# DriverForDisplayV2.net
KiCad netlist of a schematic drawn in Altium Designer
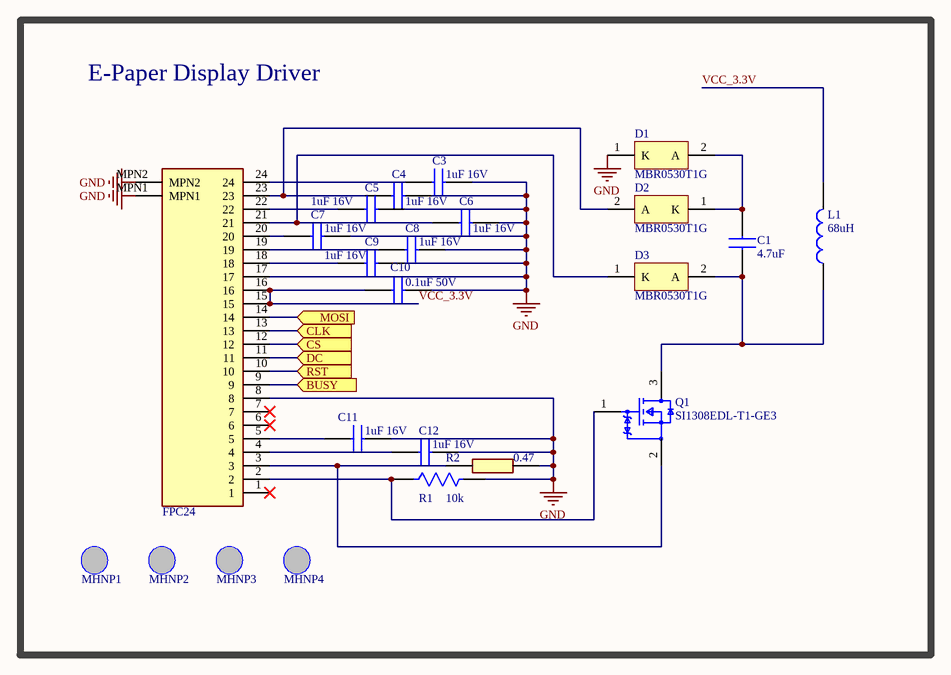
[diagram p0: DriverForDisplayV2.SchDoc]

(export (version "E")
  (design (tool "Eeschema 10.0.6"))
  (components
    (comp (ref "C1")
      (value "4.7uF")
      (footprint "SamacSys:CAPC1608X90N")
      (description "Capacitor")
      (fields
        (field (name "MANUFACTURER_PART_NUMBER") "CL10A475KO8NNNC")
        (field (name "MOUSER PART NUMBER") "187-CL10A475KO8NNNC")
      )
      (libsource (lib "*") (part "CL10A475KO8NNNC"))
    )
    (comp (ref "C3")
      (value "1uF 16V")
      (footprint "CAPC1608X90N")
      (fields
        (field (name "MANUFACTURER_PART_NUMBER") "CL10A105KO8NNNC")
        (field (name "MOUSER PART NUMBER") "187-CL10A105KO8NNNC")
      )
      (libsource (lib "Integrated_Library1") (part "CL10A105KO8NNNC"))
    )
    (comp (ref "C4")
      (value "1uF 16V")
      (footprint "CAPC1608X90N")
      (fields
        (field (name "MANUFACTURER_PART_NUMBER") "CL10A105KO8NNNC")
        (field (name "MOUSER PART NUMBER") "187-CL10A105KO8NNNC")
      )
      (libsource (lib "Integrated_Library1") (part "CL10A105KO8NNNC"))
    )
    (comp (ref "C5")
      (value "1uF 16V")
      (footprint "CAPC1608X90N")
      (fields
        (field (name "MANUFACTURER_PART_NUMBER") "CL10A105KO8NNNC")
        (field (name "MOUSER PART NUMBER") "187-CL10A105KO8NNNC")
      )
      (libsource (lib "Integrated_Library1") (part "CL10A105KO8NNNC"))
    )
    (comp (ref "C6")
      (value "1uF 16V")
      (footprint "CAPC1608X90N")
      (fields
        (field (name "MANUFACTURER_PART_NUMBER") "CL10A105KO8NNNC")
        (field (name "MOUSER PART NUMBER") "187-CL10A105KO8NNNC")
      )
      (libsource (lib "Integrated_Library1") (part "CL10A105KO8NNNC"))
    )
    (comp (ref "C7")
      (value "1uF 16V")
      (footprint "CAPC1608X90N")
      (fields
        (field (name "MANUFACTURER_PART_NUMBER") "CL10A105KO8NNNC")
        (field (name "MOUSER PART NUMBER") "187-CL10A105KO8NNNC")
      )
      (libsource (lib "Integrated_Library1") (part "CL10A105KO8NNNC"))
    )
    (comp (ref "C8")
      (value "1uF 16V")
      (footprint "CAPC1608X90N")
      (fields
        (field (name "MANUFACTURER_PART_NUMBER") "CL10A105KO8NNNC")
        (field (name "MOUSER PART NUMBER") "187-CL10A105KO8NNNC")
      )
      (libsource (lib "Integrated_Library1") (part "CL10A105KO8NNNC"))
    )
    (comp (ref "C9")
      (value "1uF 16V")
      (footprint "CAPC1608X90N")
      (fields
        (field (name "MANUFACTURER_PART_NUMBER") "CL10A105KO8NNNC")
        (field (name "MOUSER PART NUMBER") "187-CL10A105KO8NNNC")
      )
      (libsource (lib "Integrated_Library1") (part "CL10A105KO8NNNC"))
    )
    (comp (ref "C10")
      (value "0.1uF 50V")
      (footprint "CAPC1608X90N")
      (fields
        (field (name "MANUFACTURER_PART_NUMBER") "CL10A105KO8NNNC")
        (field (name "MOUSER PART NUMBER") "187-CL10A105KO8NNNC")
      )
      (libsource (lib "Integrated_Library1") (part "CL10A105KO8NNNC"))
    )
    (comp (ref "C11")
      (value "1uF 16V")
      (footprint "CAPC1608X90N")
      (fields
        (field (name "MANUFACTURER_PART_NUMBER") "CL10A105KO8NNNC")
        (field (name "MOUSER PART NUMBER") "187-CL10A105KO8NNNC")
      )
      (libsource (lib "Integrated_Library1") (part "CL10A105KO8NNNC"))
    )
    (comp (ref "C12")
      (value "1uF 16V")
      (footprint "CAPC1608X90N")
      (fields
        (field (name "MANUFACTURER_PART_NUMBER") "CL10A105KO8NNNC")
        (field (name "MOUSER PART NUMBER") "187-CL10A105KO8NNNC")
      )
      (libsource (lib "Integrated_Library1") (part "CL10A105KO8NNNC"))
    )
    (comp (ref "D1")
      (value "MBR0530T1G")
      (footprint "ONSC-SOD-123-2-425-04_V")
      (fields (field (name "MANUFACTURER") "On Semiconductor"))
      (libsource (lib "Altium Content Vault") (part "ONSC-D-K1A2-2_A"))
    )
    (comp (ref "D2")
      (value "MBR0530T1G")
      (footprint "ONSC-SOD-123-2-425-04_V")
      (fields (field (name "MANUFACTURER") "On Semiconductor"))
      (libsource (lib "") (part "ONSC-D-K1A2-2_A_1"))
    )
    (comp (ref "D3")
      (value "MBR0530T1G")
      (footprint "ONSC-SOD-123-2-425-04_V")
      (fields (field (name "MANUFACTURER") "On Semiconductor"))
      (libsource (lib "Altium Content Vault") (part "ONSC-D-K1A2-2_A"))
    )
    (comp (ref "J2")
      (value "FPC24")
      (footprint "SamacSys:FH34SRJ24S05SH50")
      (description "Connector")
      (fields
        (field (name "MANUFACTURER_PART_NUMBER") "FH34SRJ-24S-0.5SH(50)")
        (field (name "MOUSER PART NUMBER") "798-FH34SRJ24S05SH50")
      )
      (libsource (lib "*") (part "FH34SRJ-24S-0.5SH_50_"))
    )
    (comp (ref "L1")
      (value "68uH")
      (footprint "SamacSys:INDC2012X145N")
      (description "Inductor")
      (fields
        (field (name "MANUFACTURER_PART_NUMBER") "MLF2012C680KT000")
        (field (name "MOUSER PART NUMBER") "810-MLF2012C680KT000")
      )
      (libsource (lib "*") (part "MLF2012C680KT000"))
    )
    (comp (ref "MHNP1")
      (value "CMP-011-000000-1")
      (footprint "MTHNP3P2MM")
      (description "Mounting Hole Non-Plated 3.2 mm drill hole")
      (libsource (lib "timothy") (part "MTHNP3P2MM"))
    )
    (comp (ref "MHNP2")
      (value "CMP-011-000000-1")
      (footprint "MTHNP3P2MM")
      (description "Mounting Hole Non-Plated 3.2 mm drill hole")
      (libsource (lib "timothy") (part "MTHNP3P2MM"))
    )
    (comp (ref "MHNP3")
      (value "CMP-011-000000-1")
      (footprint "MTHNP3P2MM")
      (description "Mounting Hole Non-Plated 3.2 mm drill hole")
      (libsource (lib "timothy") (part "MTHNP3P2MM"))
    )
    (comp (ref "MHNP4")
      (value "CMP-011-000000-1")
      (footprint "MTHNP3P2MM")
      (description "Mounting Hole Non-Plated 3.2 mm drill hole")
      (libsource (lib "timothy") (part "MTHNP3P2MM"))
    )
    (comp (ref "Q1")
      (value "SI1308EDL-T1-GE3")
      (footprint "FP-5549-MFG")
      (description "MOSFET N-CH 30V 1.4A SC-70-3")
      (libsource (lib "Altium Content Vault") (part "e96677422f20f20903245877d22b385"))
    )
    (comp (ref "R1")
      (value "10k")
      (footprint "FP-RC1608-MFG")
      (description "Res Thick Film 0603 10kΩ 1% 0.1W ±100ppm/°C Molded SMD T/R")
      (fields (field (name "TOLERANCE") "1%"))
      (libsource (lib "Altium Content Vault") (part "1029c3af85768c4190bb7ad29bc67b5"))
    )
    (comp (ref "R2")
      (value "0.47")
      (footprint "SamacSys:RESC1608X55N")
      (description "RES, 0603, 0.47 ohm, 5%, 0.1W")
      (fields (field (name "MANUFACTURER_PART_NUMBER") "RMCF0603JTR470"))
      (libsource (lib "*") (part "RMCF0603JTR470"))
    )
  )
  (nets
    (net (code "1") (name "/BUSY") (class "Default")
      (node (ref "J2") (pin "9") (pinfunction "9_9") (pintype "passive"))
    )
    (net (code "2") (name "/CLK") (class "Default")
      (node (ref "J2") (pin "13") (pinfunction "13_13") (pintype "passive"))
    )
    (net (code "3") (name "/CS") (class "Default")
      (node (ref "J2") (pin "12") (pinfunction "12_12") (pintype "passive"))
    )
    (net (code "4") (name "/DC") (class "Default")
      (node (ref "J2") (pin "11") (pinfunction "11_11") (pintype "passive"))
    )
    (net (code "5") (name "/MOSI") (class "Default")
      (node (ref "J2") (pin "14") (pinfunction "14_14") (pintype "passive"))
    )
    (net (code "6") (name "/RST") (class "Default")
      (node (ref "J2") (pin "10") (pinfunction "10_10") (pintype "passive"))
    )
    (net (code "7") (name "/VCC_3.3V") (class "Default")
      (node (ref "C10") (pin "1") (pinfunction "1_1") (pintype "passive"))
      (node (ref "J2") (pin "15") (pinfunction "15_15") (pintype "passive"))
      (node (ref "J2") (pin "16") (pinfunction "16_16") (pintype "passive"))
      (node (ref "L1") (pin "2") (pinfunction "2_2") (pintype "passive"))
    )
    (net (code "8") (name "GND") (class "Default")
      (node (ref "C10") (pin "2") (pinfunction "2_2") (pintype "passive"))
      (node (ref "C11") (pin "2") (pinfunction "2_2") (pintype "passive"))
      (node (ref "C12") (pin "2") (pinfunction "2_2") (pintype "passive"))
      (node (ref "C3") (pin "2") (pinfunction "2_2") (pintype "passive"))
      (node (ref "C4") (pin "2") (pinfunction "2_2") (pintype "passive"))
      (node (ref "C5") (pin "2") (pinfunction "2_2") (pintype "passive"))
      (node (ref "C6") (pin "2") (pinfunction "2_2") (pintype "passive"))
      (node (ref "C7") (pin "2") (pinfunction "2_2") (pintype "passive"))
      (node (ref "C8") (pin "2") (pinfunction "2_2") (pintype "passive"))
      (node (ref "C9") (pin "2") (pinfunction "2_2") (pintype "passive"))
      (node (ref "D1") (pin "1") (pinfunction "K_1") (pintype "passive"))
      (node (ref "J2") (pin "17") (pinfunction "17_17") (pintype "passive"))
      (node (ref "J2") (pin "8") (pinfunction "8_8") (pintype "passive"))
      (node (ref "J2") (pin "MPN1") (pinfunction "MPN1_MPN1") (pintype "passive"))
      (node (ref "J2") (pin "MPN2") (pinfunction "MPN2_MPN2") (pintype "passive"))
      (node (ref "R1") (pin "2") (pinfunction "2_2") (pintype "passive"))
      (node (ref "R2") (pin "2") (pinfunction "2_2") (pintype "passive"))
    )
    (net (code "9") (name "Net-(C3-Pad1)") (class "Default")
      (node (ref "C3") (pin "1") (pinfunction "1_1") (pintype "passive"))
      (node (ref "J2") (pin "24") (pinfunction "24_24") (pintype "passive"))
    )
    (net (code "10") (name "Net-(C5-Pad1)") (class "Default")
      (node (ref "C5") (pin "1") (pinfunction "1_1") (pintype "passive"))
      (node (ref "J2") (pin "22") (pinfunction "22_22") (pintype "passive"))
    )
    (net (code "11") (name "Net-(C7-Pad1)") (class "Default")
      (node (ref "C7") (pin "1") (pinfunction "1_1") (pintype "passive"))
      (node (ref "J2") (pin "20") (pinfunction "20_20") (pintype "passive"))
    )
    (net (code "12") (name "Net-(C8-Pad1)") (class "Default")
      (node (ref "C8") (pin "1") (pinfunction "1_1") (pintype "passive"))
      (node (ref "J2") (pin "19") (pinfunction "19_19") (pintype "passive"))
    )
    (net (code "13") (name "Net-(C9-Pad1)") (class "Default")
      (node (ref "C9") (pin "1") (pinfunction "1_1") (pintype "passive"))
      (node (ref "J2") (pin "18") (pinfunction "18_18") (pintype "passive"))
    )
    (net (code "14") (name "Net-(C11-Pad1)") (class "Default")
      (node (ref "C11") (pin "1") (pinfunction "1_1") (pintype "passive"))
      (node (ref "J2") (pin "5") (pinfunction "5_5") (pintype "passive"))
    )
    (net (code "15") (name "Net-(C12-Pad1)") (class "Default")
      (node (ref "C12") (pin "1") (pinfunction "1_1") (pintype "passive"))
      (node (ref "J2") (pin "4") (pinfunction "4_4") (pintype "passive"))
    )
    (net (code "16") (name "Net-(D1-A)") (class "Default")
      (node (ref "C1") (pin "2") (pinfunction "2_2") (pintype "passive"))
      (node (ref "D1") (pin "2") (pinfunction "A_2") (pintype "passive"))
      (node (ref "D2") (pin "1") (pinfunction "K_1") (pintype "passive"))
    )
    (net (code "17") (name "Net-(D2-A)") (class "Default")
      (node (ref "C4") (pin "1") (pinfunction "1_1") (pintype "passive"))
      (node (ref "D2") (pin "2") (pinfunction "A_2") (pintype "passive"))
      (node (ref "J2") (pin "23") (pinfunction "23_23") (pintype "passive"))
    )
    (net (code "18") (name "Net-(D3-A)") (class "Default")
      (node (ref "C1") (pin "1") (pinfunction "1_1") (pintype "passive"))
      (node (ref "D3") (pin "2") (pinfunction "A_2") (pintype "passive"))
      (node (ref "L1") (pin "1") (pinfunction "1_1") (pintype "passive"))
      (node (ref "Q1") (pin "3") (pinfunction "D_3") (pintype "passive"))
    )
    (net (code "19") (name "Net-(D3-K)") (class "Default")
      (node (ref "C6") (pin "1") (pinfunction "1_1") (pintype "passive"))
      (node (ref "D3") (pin "1") (pinfunction "K_1") (pintype "passive"))
      (node (ref "J2") (pin "21") (pinfunction "21_21") (pintype "passive"))
    )
    (net (code "20") (name "Net-(Q1-G)") (class "Default")
      (node (ref "J2") (pin "2") (pinfunction "2_2") (pintype "passive"))
      (node (ref "Q1") (pin "1") (pinfunction "G_1") (pintype "passive"))
      (node (ref "R1") (pin "1") (pinfunction "1_1") (pintype "passive"))
    )
    (net (code "21") (name "Net-(Q1-S)") (class "Default")
      (node (ref "J2") (pin "3") (pinfunction "3_3") (pintype "passive"))
      (node (ref "Q1") (pin "2") (pinfunction "S_2") (pintype "passive"))
      (node (ref "R2") (pin "1") (pinfunction "1_1") (pintype "passive"))
    )
    (net (code "22") (name "unconnected-(J2-Pad1)") (class "Default")
      (node (ref "J2") (pin "1") (pinfunction "1_1") (pintype "passive+no_connect"))
    )
    (net (code "23") (name "unconnected-(J2-Pad6)") (class "Default")
      (node (ref "J2") (pin "6") (pinfunction "6_6") (pintype "passive+no_connect"))
    )
    (net (code "24") (name "unconnected-(J2-Pad7)") (class "Default")
      (node (ref "J2") (pin "7") (pinfunction "7_7") (pintype "passive+no_connect"))
    )
  )
)
